# bitponics.net
KiCad netlist of a schematic drawn in EAGLE
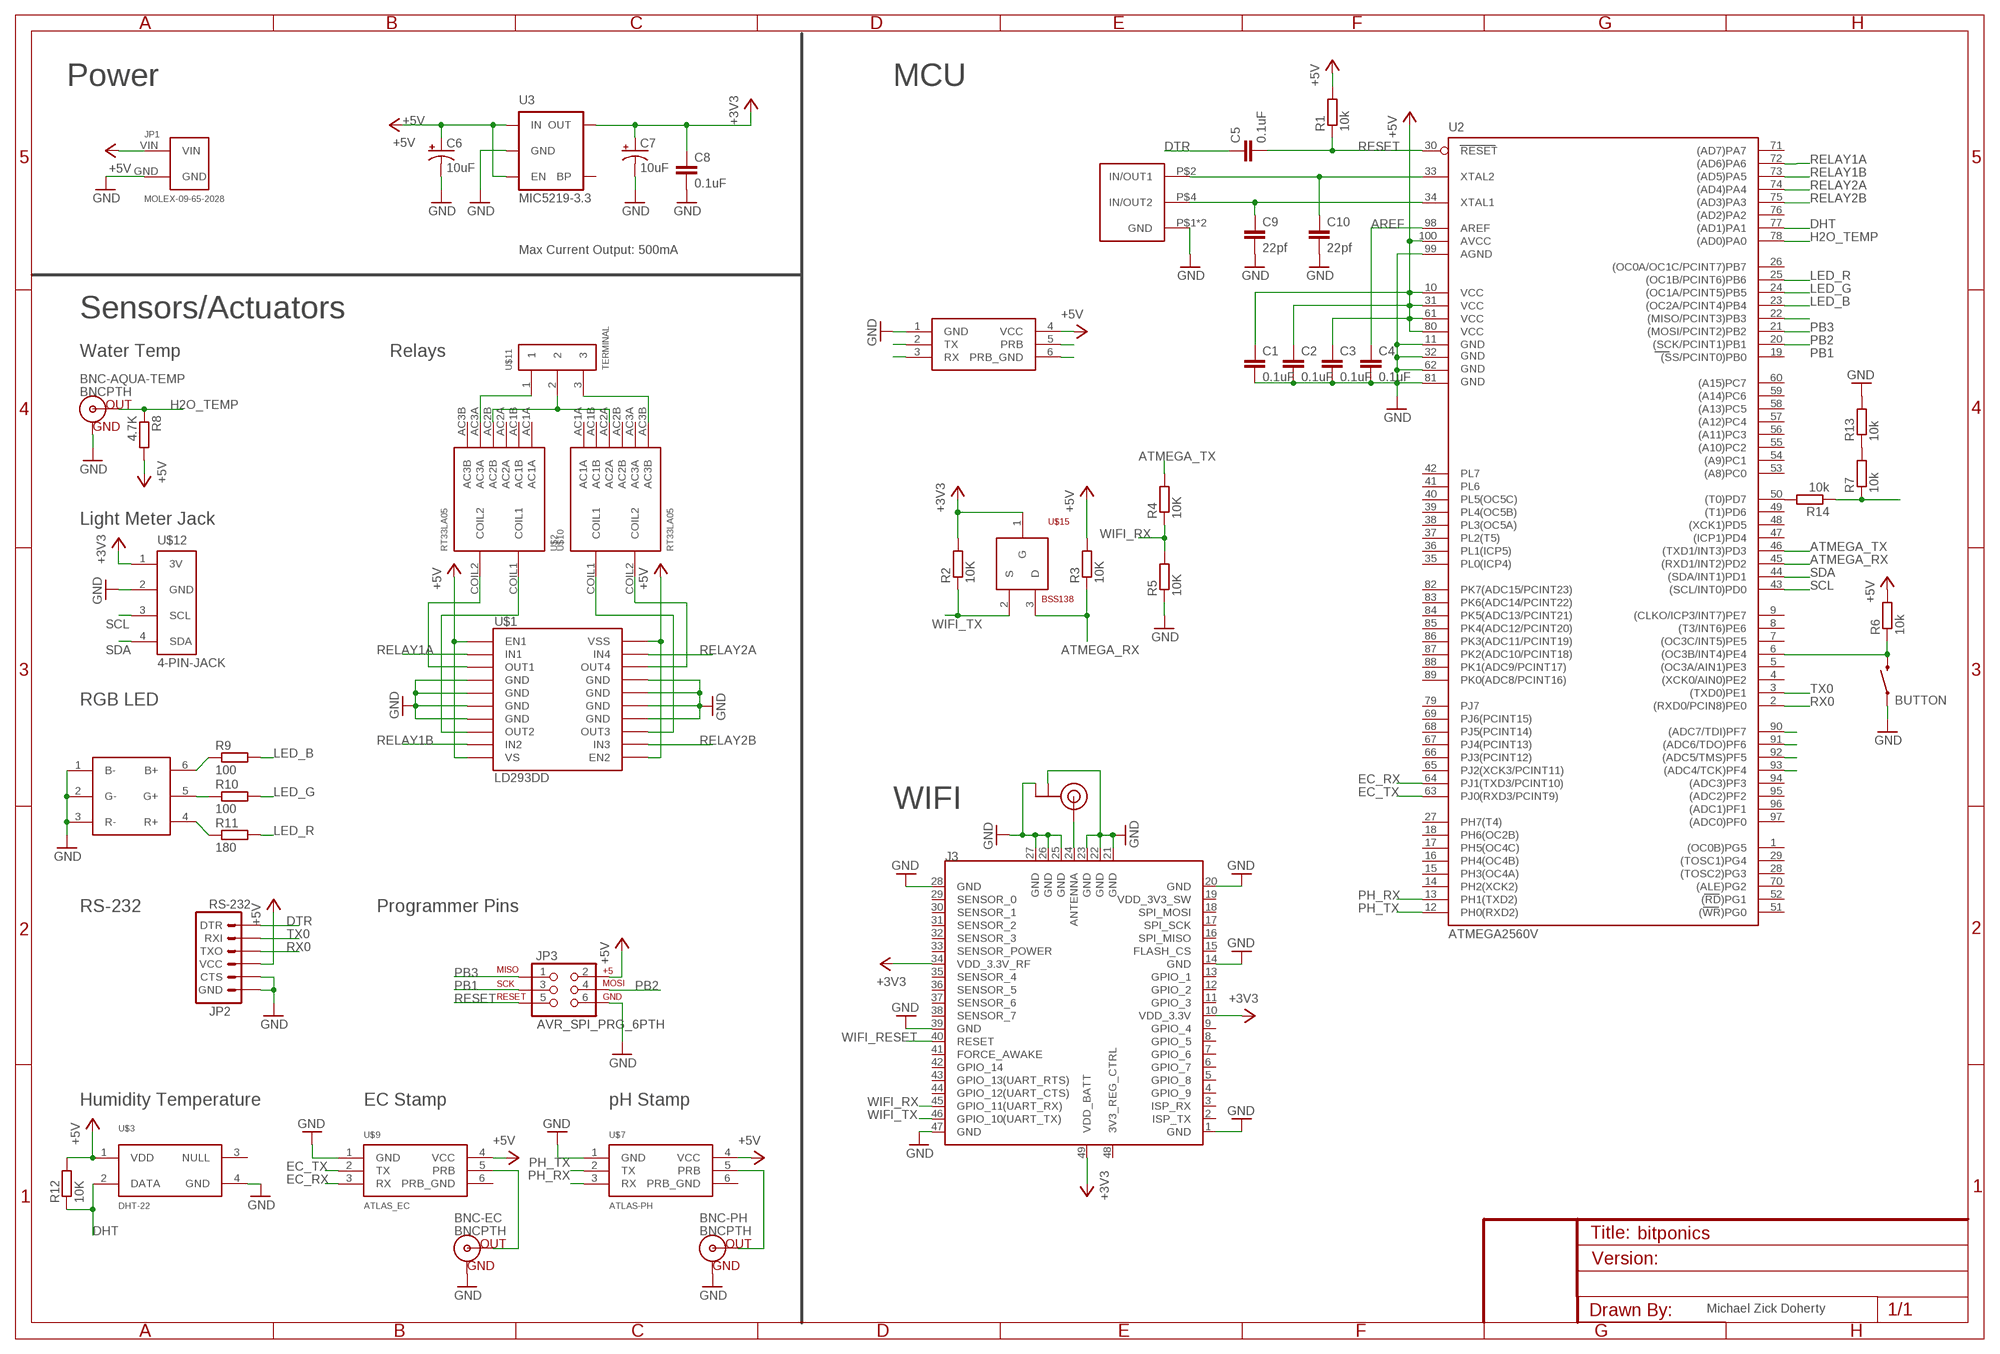
[diagram p0: schematic, sheet 1]

(export (version "E")
  (design (tool "Eeschema 10.0.6"))
  (components
    (comp (ref "BNC-AQUA-TEMP")
      (value "BNCPTH")
      (footprint "eagle-import:BNC")
      (libsource (lib "eagle-import") (part "BNCPTH"))
    )
    (comp (ref "BNC-EC")
      (value "BNCPTH")
      (footprint "eagle-import:BNC")
      (libsource (lib "eagle-import") (part "BNCPTH"))
    )
    (comp (ref "BNC-PH")
      (value "BNCPTH")
      (footprint "eagle-import:BNC")
      (libsource (lib "eagle-import") (part "BNCPTH"))
    )
    (comp (ref "BUTTON")
      (value "FSMRA2JH")
      (footprint "eagle-import:FSMRA2JH")
      (libsource (lib "eagle-import") (part "FSMRA2JH"))
    )
    (comp (ref "C1")
      (value "0.1uF")
      (footprint "eagle-import:C0603")
      (libsource (lib "eagle-import") (part "C-EUC0603"))
    )
    (comp (ref "C2")
      (value "0.1uF")
      (footprint "eagle-import:C0603")
      (libsource (lib "eagle-import") (part "C-EUC0603"))
    )
    (comp (ref "C3")
      (value "0.1uF")
      (footprint "eagle-import:C0603")
      (libsource (lib "eagle-import") (part "C-EUC0603"))
    )
    (comp (ref "C4")
      (value "0.1uF")
      (footprint "eagle-import:C0603")
      (libsource (lib "eagle-import") (part "C-EUC0603"))
    )
    (comp (ref "C5")
      (value "0.1uF")
      (footprint "eagle-import:C0603")
      (libsource (lib "eagle-import") (part "C-EUC0603"))
    )
    (comp (ref "C6")
      (value "10uF")
      (footprint "eagle-import:EIA3216")
      (libsource (lib "eagle-import") (part "CAP_POL1206"))
    )
    (comp (ref "C7")
      (value "10uF")
      (footprint "eagle-import:EIA3216")
      (libsource (lib "eagle-import") (part "CAP_POL1206"))
    )
    (comp (ref "C8")
      (value "0.1uF")
      (footprint "eagle-import:C0603")
      (libsource (lib "eagle-import") (part "C-EUC0603"))
    )
    (comp (ref "C9")
      (value "22pf")
      (footprint "eagle-import:C0603")
      (libsource (lib "eagle-import") (part "C-EUC0603"))
    )
    (comp (ref "C10")
      (value "22pf")
      (footprint "eagle-import:C0603")
      (libsource (lib "eagle-import") (part "C-EUC0603"))
    )
    (comp (ref "J3")
      (value "WIFI-RN-171")
      (footprint "eagle-import:49P-1.27-26.67X17.78")
      (libsource (lib "eagle-import") (part "WIFI-RN-171"))
    )
    (comp (ref "JP1")
      (value "MOLEX-09-65-2028")
      (footprint "eagle-import:09-65-2028")
      (libsource (lib "eagle-import") (part "MOLEX-09-65-2028"))
    )
    (comp (ref "JP2")
      (value "RS-232")
      (footprint "eagle-import:1X06_LOCK")
      (libsource (lib "eagle-import") (part "ARDUINO_SERIAL_PROGRAMLOCK"))
    )
    (comp (ref "JP3")
      (value "AVR_SPI_PRG_6PTH")
      (footprint "eagle-import:2X3")
      (libsource (lib "eagle-import") (part "AVR_SPI_PRG_6PTH"))
    )
    (comp (ref "R1")
      (value "10k")
      (footprint "eagle-import:R0603")
      (libsource (lib "eagle-import") (part "R-EU_R0603"))
    )
    (comp (ref "R2")
      (value "10K")
      (footprint "eagle-import:R0603")
      (libsource (lib "eagle-import") (part "R-EU_R0603"))
    )
    (comp (ref "R3")
      (value "10K")
      (footprint "eagle-import:R0603")
      (libsource (lib "eagle-import") (part "R-EU_R0603"))
    )
    (comp (ref "R4")
      (value "10K")
      (footprint "eagle-import:R0603")
      (libsource (lib "eagle-import") (part "R-EU_R0603"))
    )
    (comp (ref "R5")
      (value "10K")
      (footprint "eagle-import:R0603")
      (libsource (lib "eagle-import") (part "R-EU_R0603"))
    )
    (comp (ref "R6")
      (value "10k")
      (footprint "eagle-import:R0603")
      (libsource (lib "eagle-import") (part "R-EU_R0603"))
    )
    (comp (ref "R7")
      (value "10k")
      (footprint "eagle-import:R0603")
      (libsource (lib "eagle-import") (part "R-EU_R0603"))
    )
    (comp (ref "R8")
      (value "4.7K")
      (footprint "eagle-import:R0603")
      (libsource (lib "eagle-import") (part "R-EU_R0603"))
    )
    (comp (ref "R9")
      (value "100")
      (footprint "eagle-import:R0603")
      (libsource (lib "eagle-import") (part "R-EU_R0603"))
    )
    (comp (ref "R10")
      (value "100")
      (footprint "eagle-import:R0603")
      (libsource (lib "eagle-import") (part "R-EU_R0603"))
    )
    (comp (ref "R11")
      (value "180")
      (footprint "eagle-import:R0603")
      (libsource (lib "eagle-import") (part "R-EU_R0603"))
    )
    (comp (ref "R12")
      (value "10K")
      (footprint "eagle-import:R0603")
      (libsource (lib "eagle-import") (part "R-EU_R0603"))
    )
    (comp (ref "R13")
      (value "10k")
      (footprint "eagle-import:R0603")
      (libsource (lib "eagle-import") (part "R-EU_R0603"))
    )
    (comp (ref "R14")
      (value "10k")
      (footprint "eagle-import:R0603")
      (libsource (lib "eagle-import") (part "R-EU_R0603"))
    )
    (comp (ref "U$1")
      (value "LD293DD")
      (footprint "eagle-import:SO-20LD")
      (libsource (lib "eagle-import") (part "LD293DD"))
    )
    (comp (ref "U$2")
      (value "RT33LA05")
      (footprint "eagle-import:RT33LA05")
      (libsource (lib "eagle-import") (part "RT33LA05"))
    )
    (comp (ref "U$3")
      (value "DHT-22")
      (footprint "eagle-import:DHT22")
      (libsource (lib "eagle-import") (part "DHT-22"))
    )
    (comp (ref "U$4")
      (value "ATLAS-PH")
      (footprint "eagle-import:PH")
      (libsource (lib "eagle-import") (part "ATLAS-PH"))
    )
    (comp (ref "U$5")
      (value "U.FL")
      (footprint "eagle-import:U.FL")
      (libsource (lib "eagle-import") (part "U.FL"))
    )
    (comp (ref "U$6")
      (value "ECX-32")
      (footprint "eagle-import:ECX-32")
      (libsource (lib "eagle-import") (part "ECX-32"))
    )
    (comp (ref "U$7")
      (value "ATLAS-PH")
      (footprint "eagle-import:PH")
      (libsource (lib "eagle-import") (part "ATLAS-PH"))
    )
    (comp (ref "U$9")
      (value "ATLAS_EC")
      (footprint "eagle-import:EC")
      (libsource (lib "eagle-import") (part "ATLAS_EC"))
    )
    (comp (ref "U$10")
      (value "RT33LA05")
      (footprint "eagle-import:RT33LA05")
      (libsource (lib "eagle-import") (part "RT33LA05"))
    )
    (comp (ref "U$11")
      (value "TERMINAL")
      (footprint "eagle-import:TERMINAL")
      (libsource (lib "eagle-import") (part "TERMINAL"))
    )
    (comp (ref "U$12")
      (value "4-PIN-JACK")
      (footprint "eagle-import:4-PIN-JACK")
      (libsource (lib "eagle-import") (part "4-PIN-JACK"))
    )
    (comp (ref "U$15")
      (value "BSS138")
      (footprint "eagle-import:SOT23")
      (libsource (lib "eagle-import") (part "BSS138"))
    )
    (comp (ref "U2")
      (value "ATMEGA2560AU")
      (footprint "eagle-import:TQFP100")
      (libsource (lib "eagle-import") (part "ATMEGA2560AU"))
    )
    (comp (ref "U3")
      (value "V_REG_LDOSMD")
      (footprint "eagle-import:SOT23-5")
      (libsource (lib "eagle-import") (part "V_REG_LDOSMD"))
    )
    (comp (ref "U13")
      (value "RGB-LED")
      (footprint "eagle-import:RGB-LED")
      (libsource (lib "eagle-import") (part "RGB-LED"))
    )
  )
  (nets
    (net (code "1") (name "+3V3") (class "Default")
      (node (ref "C7") (pin "A") (pinfunction "+_A") (pintype "passive"))
      (node (ref "C8") (pin "1") (pinfunction "1_1") (pintype "passive"))
      (node (ref "J3") (pin "10") (pinfunction "VDD_3.3V_10") (pintype "power_in"))
      (node (ref "J3") (pin "34") (pinfunction "VDD_3.3V_RF_34") (pintype "power_in"))
      (node (ref "J3") (pin "49") (pinfunction "VDD_BATT_49") (pintype "bidirectional"))
      (node (ref "R2") (pin "2") (pinfunction "2_2") (pintype "passive"))
      (node (ref "U$12") (pin "1") (pinfunction "3V_1") (pintype "bidirectional"))
      (node (ref "U$15") (pin "1") (pinfunction "G_1") (pintype "bidirectional"))
      (node (ref "U3") (pin "5") (pinfunction "OUT_5") (pintype "passive"))
    )
    (net (code "2") (name "+5V") (class "Default")
      (node (ref "C1") (pin "1") (pinfunction "1_1") (pintype "passive"))
      (node (ref "C2") (pin "1") (pinfunction "1_1") (pintype "passive"))
      (node (ref "C3") (pin "1") (pinfunction "1_1") (pintype "passive"))
      (node (ref "C6") (pin "A") (pinfunction "+_A") (pintype "passive"))
      (node (ref "JP1") (pin "VIN") (pinfunction "VIN_VIN") (pintype "bidirectional"))
      (node (ref "JP2") (pin "4") (pinfunction "VCC_4") (pintype "passive"))
      (node (ref "JP3") (pin "2") (pinfunction "2_2") (pintype "passive"))
      (node (ref "R1") (pin "2") (pinfunction "2_2") (pintype "passive"))
      (node (ref "R12") (pin "2") (pinfunction "2_2") (pintype "passive"))
      (node (ref "R3") (pin "2") (pinfunction "2_2") (pintype "passive"))
      (node (ref "R6") (pin "2") (pinfunction "2_2") (pintype "passive"))
      (node (ref "R8") (pin "2") (pinfunction "2_2") (pintype "passive"))
      (node (ref "U$1") (pin "1") (pinfunction "EN1_1") (pintype "bidirectional"))
      (node (ref "U$1") (pin "10") (pinfunction "VS_10") (pintype "bidirectional"))
      (node (ref "U$1") (pin "11") (pinfunction "EN2_11") (pintype "bidirectional"))
      (node (ref "U$1") (pin "20") (pinfunction "VSS_20") (pintype "bidirectional"))
      (node (ref "U$3") (pin "1") (pinfunction "VDD_1") (pintype "bidirectional"))
      (node (ref "U$4") (pin "4") (pinfunction "VCC_4") (pintype "bidirectional"))
      (node (ref "U$7") (pin "4") (pinfunction "VCC_4") (pintype "bidirectional"))
      (node (ref "U$9") (pin "4") (pinfunction "VCC_4") (pintype "bidirectional"))
      (node (ref "U2") (pin "10") (pinfunction "VCC_10") (pintype "power_in"))
      (node (ref "U2") (pin "100") (pinfunction "AVCC_100") (pintype "power_in"))
      (node (ref "U2") (pin "31") (pinfunction "VCC1_31") (pintype "power_in"))
      (node (ref "U2") (pin "61") (pinfunction "VCC2_61") (pintype "power_in"))
      (node (ref "U2") (pin "80") (pinfunction "VCC3_80") (pintype "power_in"))
      (node (ref "U3") (pin "1") (pinfunction "IN_1") (pintype "input"))
      (node (ref "U3") (pin "3") (pinfunction "EN_3") (pintype "input"))
    )
    (net (code "3") (name "/A4") (class "Default")
      (node (ref "U$4") (pin "5") (pinfunction "PRB_5") (pintype "bidirectional"))
      (node (ref "U2") (pin "93") (pinfunction "(ADC4/TCK)PF4_93") (pintype "bidirectional"))
    )
    (net (code "4") (name "/A5") (class "Default")
      (node (ref "U$4") (pin "6") (pinfunction "PRB_GND_6") (pintype "bidirectional"))
      (node (ref "U2") (pin "92") (pinfunction "(ADC5/TMS)PF5_92") (pintype "bidirectional"))
    )
    (net (code "5") (name "/A6") (class "Default")
      (node (ref "U$4") (pin "3") (pinfunction "RX_3") (pintype "bidirectional"))
      (node (ref "U2") (pin "91") (pinfunction "(ADC6/TDO)PF6_91") (pintype "bidirectional"))
    )
    (net (code "6") (name "/A7") (class "Default")
      (node (ref "U$4") (pin "2") (pinfunction "TX_2") (pintype "bidirectional"))
      (node (ref "U2") (pin "90") (pinfunction "(ADC7/TDI)PF7_90") (pintype "bidirectional"))
    )
    (net (code "7") (name "/AREF") (class "Default")
      (node (ref "C4") (pin "1") (pinfunction "1_1") (pintype "passive"))
      (node (ref "U2") (pin "98") (pinfunction "AREF_98") (pintype "bidirectional"))
    )
    (net (code "8") (name "/ATMEGA_RX") (class "Default")
      (node (ref "R3") (pin "1") (pinfunction "1_1") (pintype "passive"))
      (node (ref "U$15") (pin "3") (pinfunction "D_3") (pintype "bidirectional"))
      (node (ref "U2") (pin "45") (pinfunction "(RXD1/INT2)PD2_45") (pintype "bidirectional"))
    )
    (net (code "9") (name "/ATMEGA_TX") (class "Default")
      (node (ref "R4") (pin "2") (pinfunction "2_2") (pintype "passive"))
      (node (ref "U2") (pin "46") (pinfunction "(TXD1/INT3)PD3_46") (pintype "bidirectional"))
    )
    (net (code "10") (name "/DHT") (class "Default")
      (node (ref "R12") (pin "1") (pinfunction "1_1") (pintype "passive"))
      (node (ref "U$3") (pin "2") (pinfunction "DATA_2") (pintype "bidirectional"))
      (node (ref "U2") (pin "77") (pinfunction "(AD1)PA1_77") (pintype "bidirectional"))
    )
    (net (code "11") (name "/DTR") (class "Default")
      (node (ref "C5") (pin "1") (pinfunction "1_1") (pintype "passive"))
      (node (ref "JP2") (pin "1") (pinfunction "DTR_1") (pintype "passive"))
    )
    (net (code "12") (name "/EC_RX") (class "Default")
      (node (ref "U$9") (pin "3") (pinfunction "RX_3") (pintype "bidirectional"))
      (node (ref "U2") (pin "64") (pinfunction "PJ1(TXD3/PCINT10)_64") (pintype "bidirectional"))
    )
    (net (code "13") (name "/EC_TX") (class "Default")
      (node (ref "U$9") (pin "2") (pinfunction "TX_2") (pintype "bidirectional"))
      (node (ref "U2") (pin "63") (pinfunction "PJ0(RXD3/PCINT9)_63") (pintype "bidirectional"))
    )
    (net (code "14") (name "/H2O_TEMP") (class "Default")
      (node (ref "BNC-AQUA-TEMP") (pin "S") (pinfunction "OUT_S") (pintype "bidirectional"))
      (node (ref "R8") (pin "1") (pinfunction "1_1") (pintype "passive"))
      (node (ref "U2") (pin "78") (pinfunction "(AD0)PA0_78") (pintype "bidirectional"))
    )
    (net (code "15") (name "/LED_B") (class "Default")
      (node (ref "R9") (pin "2") (pinfunction "2_2") (pintype "passive"))
      (node (ref "U2") (pin "23") (pinfunction "(OC2A/PCINT4)PB4_23") (pintype "bidirectional"))
    )
    (net (code "16") (name "/LED_G") (class "Default")
      (node (ref "R10") (pin "2") (pinfunction "2_2") (pintype "passive"))
      (node (ref "U2") (pin "24") (pinfunction "(OC1A/PCINT5)PB5_24") (pintype "bidirectional"))
    )
    (net (code "17") (name "/LED_R") (class "Default")
      (node (ref "R11") (pin "2") (pinfunction "2_2") (pintype "passive"))
      (node (ref "U2") (pin "25") (pinfunction "(OC1B/PCINT6)PB6_25") (pintype "bidirectional"))
    )
    (net (code "18") (name "/PB1") (class "Default")
      (node (ref "JP3") (pin "3") (pinfunction "3_3") (pintype "passive"))
      (node (ref "U2") (pin "20") (pinfunction "(SCK/PCINT1)PB1_20") (pintype "bidirectional"))
    )
    (net (code "19") (name "/PB2") (class "Default")
      (node (ref "JP3") (pin "4") (pinfunction "4_4") (pintype "passive"))
      (node (ref "U2") (pin "21") (pinfunction "(MOSI/PCINT2)PB2_21") (pintype "bidirectional"))
    )
    (net (code "20") (name "/PB3") (class "Default")
      (node (ref "JP3") (pin "1") (pinfunction "1_1") (pintype "passive"))
      (node (ref "U2") (pin "22") (pinfunction "(MISO/PCINT3)PB3_22") (pintype "bidirectional"))
    )
    (net (code "21") (name "/PH_RX") (class "Default")
      (node (ref "U$7") (pin "3") (pinfunction "RX_3") (pintype "bidirectional"))
      (node (ref "U2") (pin "13") (pinfunction "PH1(TXD2)_13") (pintype "bidirectional"))
    )
    (net (code "22") (name "/PH_TX") (class "Default")
      (node (ref "U$7") (pin "2") (pinfunction "TX_2") (pintype "bidirectional"))
      (node (ref "U2") (pin "12") (pinfunction "PH0(RXD2)_12") (pintype "bidirectional"))
    )
    (net (code "23") (name "/RELAY1A") (class "Default")
      (node (ref "U$1") (pin "2") (pinfunction "IN1_2") (pintype "bidirectional"))
      (node (ref "U2") (pin "72") (pinfunction "(AD6)PA6_72") (pintype "bidirectional"))
    )
    (net (code "24") (name "/RELAY1B") (class "Default")
      (node (ref "U$1") (pin "9") (pinfunction "IN2_9") (pintype "bidirectional"))
      (node (ref "U2") (pin "73") (pinfunction "(AD5)PA5_73") (pintype "bidirectional"))
    )
    (net (code "25") (name "/RELAY2A") (class "Default")
      (node (ref "U$1") (pin "19") (pinfunction "IN4_19") (pintype "bidirectional"))
      (node (ref "U2") (pin "74") (pinfunction "(AD4)PA4_74") (pintype "bidirectional"))
    )
    (net (code "26") (name "/RELAY2B") (class "Default")
      (node (ref "U$1") (pin "12") (pinfunction "IN3_12") (pintype "bidirectional"))
      (node (ref "U2") (pin "75") (pinfunction "(AD3)PA3_75") (pintype "bidirectional"))
    )
    (net (code "27") (name "/RESET") (class "Default")
      (node (ref "C5") (pin "2") (pinfunction "2_2") (pintype "passive"))
      (node (ref "JP3") (pin "5") (pinfunction "5_5") (pintype "passive"))
      (node (ref "R1") (pin "1") (pinfunction "1_1") (pintype "passive"))
      (node (ref "U2") (pin "30") (pinfunction "RESET_30") (pintype "input"))
    )
    (net (code "28") (name "/RX0") (class "Default")
      (node (ref "JP2") (pin "3") (pinfunction "TXO_3") (pintype "passive"))
      (node (ref "U2") (pin "2") (pinfunction "(RXD0/PCIN8)PE0_2") (pintype "bidirectional"))
    )
    (net (code "29") (name "/SCL") (class "Default")
      (node (ref "U$12") (pin "3") (pinfunction "SCL_3") (pintype "bidirectional"))
      (node (ref "U2") (pin "43") (pinfunction "(SCL/INT0)PD0_43") (pintype "bidirectional"))
    )
    (net (code "30") (name "/SDA") (class "Default")
      (node (ref "U$12") (pin "4") (pinfunction "SDA_4") (pintype "bidirectional"))
      (node (ref "U2") (pin "44") (pinfunction "(SDA/INT1)PD1_44") (pintype "bidirectional"))
    )
    (net (code "31") (name "/TX0") (class "Default")
      (node (ref "JP2") (pin "2") (pinfunction "RXI_2") (pintype "passive"))
      (node (ref "U2") (pin "3") (pinfunction "(TXD0)PE1_3") (pintype "bidirectional"))
    )
    (net (code "32") (name "/WIFI_RESET") (class "Default")
      (node (ref "J3") (pin "40") (pinfunction "RESET_40") (pintype "input"))
      (node (ref "R14") (pin "1") (pinfunction "1_1") (pintype "passive"))
      (node (ref "R7") (pin "1") (pinfunction "1_1") (pintype "passive"))
    )
    (net (code "33") (name "/WIFI_RX") (class "Default")
      (node (ref "J3") (pin "45") (pinfunction "GPIO_11(UART_RX)_45") (pintype "bidirectional"))
      (node (ref "R4") (pin "1") (pinfunction "1_1") (pintype "passive"))
      (node (ref "R5") (pin "2") (pinfunction "2_2") (pintype "passive"))
    )
    (net (code "34") (name "/WIFI_TX") (class "Default")
      (node (ref "J3") (pin "46") (pinfunction "GPIO_10(UART_TX)_46") (pintype "bidirectional"))
      (node (ref "R2") (pin "1") (pinfunction "1_1") (pintype "passive"))
      (node (ref "U$15") (pin "2") (pinfunction "S_2") (pintype "bidirectional"))
    )
    (net (code "35") (name "GND") (class "Default")
      (node (ref "BNC-AQUA-TEMP") (pin "GND") (pinfunction "GND_GND") (pintype "bidirectional"))
      (node (ref "BNC-EC") (pin "GND") (pinfunction "GND_GND") (pintype "bidirectional"))
      (node (ref "BNC-PH") (pin "GND") (pinfunction "GND_GND") (pintype "bidirectional"))
      (node (ref "BUTTON") (pin "2A") (pinfunction "1_2A") (pintype "passive"))
      (node (ref "C1") (pin "2") (pinfunction "2_2") (pintype "passive"))
      (node (ref "C10") (pin "2") (pinfunction "2_2") (pintype "passive"))
      (node (ref "C2") (pin "2") (pinfunction "2_2") (pintype "passive"))
      (node (ref "C3") (pin "2") (pinfunction "2_2") (pintype "passive"))
      (node (ref "C4") (pin "2") (pinfunction "2_2") (pintype "passive"))
      (node (ref "C6") (pin "C") (pinfunction "-_C") (pintype "passive"))
      (node (ref "C7") (pin "C") (pinfunction "-_C") (pintype "passive"))
      (node (ref "C8") (pin "2") (pinfunction "2_2") (pintype "passive"))
      (node (ref "C9") (pin "2") (pinfunction "2_2") (pintype "passive"))
      (node (ref "J3") (pin "1") (pinfunction "GND_1") (pintype "power_in"))
      (node (ref "J3") (pin "14") (pinfunction "GND_14") (pintype "power_in"))
      (node (ref "J3") (pin "20") (pinfunction "GND_20") (pintype "power_in"))
      (node (ref "J3") (pin "21") (pinfunction "GND_21") (pintype "power_in"))
      (node (ref "J3") (pin "22") (pinfunction "GND_22") (pintype "power_in"))
      (node (ref "J3") (pin "23") (pinfunction "GND_23") (pintype "power_in"))
      (node (ref "J3") (pin "25") (pinfunction "GND_25") (pintype "power_in"))
      (node (ref "J3") (pin "26") (pinfunction "GND_26") (pintype "power_in"))
      (node (ref "J3") (pin "27") (pinfunction "GND_27") (pintype "power_in"))
      (node (ref "J3") (pin "28") (pinfunction "GND_28") (pintype "power_in"))
      (node (ref "J3") (pin "39") (pinfunction "GND_39") (pintype "power_in"))
      (node (ref "J3") (pin "47") (pinfunction "GND_47") (pintype "power_in"))
      (node (ref "JP1") (pin "GND") (pinfunction "GND_GND") (pintype "bidirectional"))
      (node (ref "JP2") (pin "5") (pinfunction "CTS_5") (pintype "passive"))
      (node (ref "JP2") (pin "6") (pinfunction "GND_6") (pintype "passive"))
      (node (ref "JP3") (pin "6") (pinfunction "6_6") (pintype "passive"))
      (node (ref "R13") (pin "2") (pinfunction "2_2") (pintype "passive"))
      (node (ref "R5") (pin "1") (pinfunction "1_1") (pintype "passive"))
      (node (ref "U$1") (pin "14") (pinfunction "GND_14") (pintype "bidirectional"))
      (node (ref "U$1") (pin "15") (pinfunction "GND_15") (pintype "bidirectional"))
      (node (ref "U$1") (pin "16") (pinfunction "GND_16") (pintype "bidirectional"))
      (node (ref "U$1") (pin "17") (pinfunction "GND_17") (pintype "bidirectional"))
      (node (ref "U$1") (pin "4") (pinfunction "GND_4") (pintype "bidirectional"))
      (node (ref "U$1") (pin "5") (pinfunction "GND_5") (pintype "bidirectional"))
      (node (ref "U$1") (pin "6") (pinfunction "GND_6") (pintype "bidirectional"))
      (node (ref "U$1") (pin "7") (pinfunction "GND_7") (pintype "bidirectional"))
      (node (ref "U$12") (pin "2") (pinfunction "GND_2") (pintype "bidirectional"))
      (node (ref "U$3") (pin "4") (pinfunction "GND_4") (pintype "bidirectional"))
      (node (ref "U$4") (pin "1") (pinfunction "GND_1") (pintype "bidirectional"))
      (node (ref "U$5") (pin "P$1") (pinfunction "GND_P$1") (pintype "bidirectional"))
      (node (ref "U$5") (pin "P$2") (pinfunction "GND_P$2") (pintype "bidirectional"))
      (node (ref "U$6") (pin "P$1") (pinfunction "GND_P$1") (pintype "bidirectional"))
      (node (ref "U$6") (pin "P$3") (pinfunction "GND_P$3") (pintype "bidirectional"))
      (node (ref "U$7") (pin "1") (pinfunction "GND_1") (pintype "bidirectional"))
      (node (ref "U$9") (pin "1") (pinfunction "GND_1") (pintype "bidirectional"))
      (node (ref "U13") (pin "1") (pinfunction "B-_1") (pintype "bidirectional"))
      (node (ref "U13") (pin "2") (pinfunction "G-_2") (pintype "bidirectional"))
      (node (ref "U13") (pin "3") (pinfunction "R-_3") (pintype "bidirectional"))
      (node (ref "U2") (pin "11") (pinfunction "GND_11") (pintype "power_in"))
      (node (ref "U2") (pin "32") (pinfunction "GND1_32") (pintype "power_in"))
      (node (ref "U2") (pin "62") (pinfunction "GND2_62") (pintype "power_in"))
      (node (ref "U2") (pin "81") (pinfunction "GND3_81") (pintype "power_in"))
      (node (ref "U2") (pin "99") (pinfunction "AGND_99") (pintype "power_in"))
      (node (ref "U3") (pin "2") (pinfunction "GND_2") (pintype "input"))
    )
    (net (code "36") (name "Net-(BNC-EC-OUT)") (class "Default")
      (node (ref "BNC-EC") (pin "S") (pinfunction "OUT_S") (pintype "bidirectional"))
      (node (ref "U$9") (pin "5") (pinfunction "PRB_5") (pintype "bidirectional"))
    )
    (net (code "37") (name "Net-(BNC-PH-OUT)") (class "Default")
      (node (ref "BNC-PH") (pin "S") (pinfunction "OUT_S") (pintype "bidirectional"))
      (node (ref "U$7") (pin "5") (pinfunction "PRB_5") (pintype "bidirectional"))
    )
    (net (code "38") (name "Net-(BUTTON-2)") (class "Default")
      (node (ref "BUTTON") (pin "2B") (pinfunction "2_2B") (pintype "passive"))
      (node (ref "R6") (pin "1") (pinfunction "1_1") (pintype "passive"))
      (node (ref "U2") (pin "6") (pinfunction "(OC3B/INT4)PE4_6") (pintype "bidirectional"))
    )
    (net (code "39") (name "Net-(J3-ANTENNA)") (class "Default")
      (node (ref "J3") (pin "24") (pinfunction "ANTENNA_24") (pintype "bidirectional"))
      (node (ref "U$5") (pin "P$3") (pinfunction "SIGNAL_P$3") (pintype "bidirectional"))
    )
    (net (code "40") (name "Net-(R13-Pad1)") (class "Default")
      (node (ref "R13") (pin "1") (pinfunction "1_1") (pintype "passive"))
      (node (ref "R7") (pin "2") (pinfunction "2_2") (pintype "passive"))
    )
    (net (code "41") (name "Net-(U$1-OUT1)") (class "Default")
      (node (ref "U$1") (pin "3") (pinfunction "OUT1_3") (pintype "bidirectional"))
      (node (ref "U$2") (pin "COIL2") (pinfunction "COIL2_COIL2") (pintype "bidirectional"))
    )
    (net (code "42") (name "Net-(U$1-OUT2)") (class "Default")
      (node (ref "U$1") (pin "8") (pinfunction "OUT2_8") (pintype "bidirectional"))
      (node (ref "U$2") (pin "COIL1") (pinfunction "COIL1_COIL1") (pintype "bidirectional"))
    )
    (net (code "43") (name "Net-(U$1-OUT3)") (class "Default")
      (node (ref "U$1") (pin "13") (pinfunction "OUT3_13") (pintype "bidirectional"))
      (node (ref "U$10") (pin "COIL1") (pinfunction "COIL1_COIL1") (pintype "bidirectional"))
    )
    (net (code "44") (name "Net-(U$1-OUT4)") (class "Default")
      (node (ref "U$1") (pin "18") (pinfunction "OUT4_18") (pintype "bidirectional"))
      (node (ref "U$10") (pin "COIL2") (pinfunction "COIL2_COIL2") (pintype "bidirectional"))
    )
    (net (code "45") (name "Net-(U$6-IN{slash}OUT1)") (class "Default")
      (node (ref "C10") (pin "1") (pinfunction "1_1") (pintype "passive"))
      (node (ref "U$6") (pin "P$2") (pinfunction "IN/OUT1_P$2") (pintype "bidirectional"))
      (node (ref "U2") (pin "33") (pinfunction "XTAL2_33") (pintype "output"))
    )
    (net (code "46") (name "Net-(U$6-IN{slash}OUT2)") (class "Default")
      (node (ref "C9") (pin "1") (pinfunction "1_1") (pintype "passive"))
      (node (ref "U$6") (pin "P$4") (pinfunction "IN/OUT2_P$4") (pintype "bidirectional"))
      (node (ref "U2") (pin "34") (pinfunction "XTAL1_34") (pintype "input"))
    )
    (net (code "47") (name "Net-(U$10-PadAC2A)") (class "Default")
      (node (ref "U$10") (pin "AC2A") (pinfunction "AC2A_AC2A") (pintype "bidirectional"))
      (node (ref "U$11") (pin "2") (pinfunction "2_2") (pintype "bidirectional"))
      (node (ref "U$2") (pin "AC2B") (pinfunction "AC2B_AC2B") (pintype "bidirectional"))
    )
    (net (code "48") (name "Net-(U$10-PadAC3B)") (class "Default")
      (node (ref "U$10") (pin "AC3B") (pinfunction "AC3B_AC3B") (pintype "bidirectional"))
      (node (ref "U$11") (pin "3") (pinfunction "3_3") (pintype "bidirectional"))
    )
    (net (code "49") (name "Net-(U$11-Pad1)") (class "Default")
      (node (ref "U$11") (pin "1") (pinfunction "1_1") (pintype "bidirectional"))
      (node (ref "U$2") (pin "AC3A") (pinfunction "AC3A_AC3A") (pintype "bidirectional"))
    )
    (net (code "50") (name "Net-(U2-(T0)PD7)") (class "Default")
      (node (ref "R14") (pin "2") (pinfunction "2_2") (pintype "passive"))
      (node (ref "U2") (pin "50") (pinfunction "(T0)PD7_50") (pintype "bidirectional"))
    )
    (net (code "51") (name "Net-(U13-B+)") (class "Default")
      (node (ref "R9") (pin "1") (pinfunction "1_1") (pintype "passive"))
      (node (ref "U13") (pin "6") (pinfunction "B+_6") (pintype "bidirectional"))
    )
    (net (code "52") (name "Net-(U13-G+)") (class "Default")
      (node (ref "R10") (pin "1") (pinfunction "1_1") (pintype "passive"))
      (node (ref "U13") (pin "5") (pinfunction "G+_5") (pintype "bidirectional"))
    )
    (net (code "53") (name "Net-(U13-R+)") (class "Default")
      (node (ref "R11") (pin "1") (pinfunction "1_1") (pintype "passive"))
      (node (ref "U13") (pin "4") (pinfunction "R+_4") (pintype "bidirectional"))
    )
    (net (code "54") (name "unconnected-(J3-3V3_REG_CTRL-Pad48)") (class "Default")
      (node (ref "J3") (pin "48") (pinfunction "3V3_REG_CTRL_48") (pintype "input"))
    )
    (net (code "55") (name "unconnected-(J3-FLASH_CS-Pad15)") (class "Default")
      (node (ref "J3") (pin "15") (pinfunction "FLASH_CS_15") (pintype "bidirectional"))
    )
    (net (code "56") (name "unconnected-(J3-FORCE_AWAKE-Pad41)") (class "Default")
      (node (ref "J3") (pin "41") (pinfunction "FORCE_AWAKE_41") (pintype "bidirectional"))
    )
    (net (code "57") (name "unconnected-(J3-GPIO_1-Pad13)") (class "Default")
      (node (ref "J3") (pin "13") (pinfunction "GPIO_1_13") (pintype "bidirectional"))
    )
    (net (code "58") (name "unconnected-(J3-GPIO_2-Pad12)") (class "Default")
      (node (ref "J3") (pin "12") (pinfunction "GPIO_2_12") (pintype "bidirectional"))
    )
    (net (code "59") (name "unconnected-(J3-GPIO_3-Pad11)") (class "Default")
      (node (ref "J3") (pin "11") (pinfunction "GPIO_3_11") (pintype "bidirectional"))
    )
    (net (code "60") (name "unconnected-(J3-GPIO_4-Pad9)") (class "Default")
      (node (ref "J3") (pin "9") (pinfunction "GPIO_4_9") (pintype "bidirectional"))
    )
    (net (code "61") (name "unconnected-(J3-GPIO_5-Pad8)") (class "Default")
      (node (ref "J3") (pin "8") (pinfunction "GPIO_5_8") (pintype "bidirectional"))
    )
    (net (code "62") (name "unconnected-(J3-GPIO_6-Pad7)") (class "Default")
      (node (ref "J3") (pin "7") (pinfunction "GPIO_6_7") (pintype "bidirectional"))
    )
    (net (code "63") (name "unconnected-(J3-GPIO_7-Pad6)") (class "Default")
      (node (ref "J3") (pin "6") (pinfunction "GPIO_7_6") (pintype "bidirectional"))
    )
    (net (code "64") (name "unconnected-(J3-GPIO_8-Pad5)") (class "Default")
      (node (ref "J3") (pin "5") (pinfunction "GPIO_8_5") (pintype "bidirectional"))
    )
    (net (code "65") (name "unconnected-(J3-GPIO_9-Pad4)") (class "Default")
      (node (ref "J3") (pin "4") (pinfunction "GPIO_9_4") (pintype "bidirectional"))
    )
    (net (code "66") (name "unconnected-(J3-GPIO_12(UART_CTS)-Pad44)") (class "Default")
      (node (ref "J3") (pin "44") (pinfunction "GPIO_12(UART_CTS)_44") (pintype "bidirectional"))
    )
    (net (code "67") (name "unconnected-(J3-GPIO_13(UART_RTS)-Pad43)") (class "Default")
      (node (ref "J3") (pin "43") (pinfunction "GPIO_13(UART_RTS)_43") (pintype "bidirectional"))
    )
    (net (code "68") (name "unconnected-(J3-GPIO_14-Pad42)") (class "Default")
      (node (ref "J3") (pin "42") (pinfunction "GPIO_14_42") (pintype "bidirectional"))
    )
    (net (code "69") (name "unconnected-(J3-ISP_RX-Pad3)") (class "Default")
      (node (ref "J3") (pin "3") (pinfunction "ISP_RX_3") (pintype "bidirectional"))
    )
    (net (code "70") (name "unconnected-(J3-ISP_TX-Pad2)") (class "Default")
      (node (ref "J3") (pin "2") (pinfunction "ISP_TX_2") (pintype "bidirectional"))
    )
    (net (code "71") (name "unconnected-(J3-SENSOR_0-Pad29)") (class "Default")
      (node (ref "J3") (pin "29") (pinfunction "SENSOR_0_29") (pintype "input"))
    )
    (net (code "72") (name "unconnected-(J3-SENSOR_1-Pad30)") (class "Default")
      (node (ref "J3") (pin "30") (pinfunction "SENSOR_1_30") (pintype "input"))
    )
    (net (code "73") (name "unconnected-(J3-SENSOR_2-Pad31)") (class "Default")
      (node (ref "J3") (pin "31") (pinfunction "SENSOR_2_31") (pintype "input"))
    )
    (net (code "74") (name "unconnected-(J3-SENSOR_3-Pad32)") (class "Default")
      (node (ref "J3") (pin "32") (pinfunction "SENSOR_3_32") (pintype "input"))
    )
    (net (code "75") (name "unconnected-(J3-SENSOR_4-Pad35)") (class "Default")
      (node (ref "J3") (pin "35") (pinfunction "SENSOR_4_35") (pintype "input"))
    )
    (net (code "76") (name "unconnected-(J3-SENSOR_5-Pad36)") (class "Default")
      (node (ref "J3") (pin "36") (pinfunction "SENSOR_5_36") (pintype "input"))
    )
    (net (code "77") (name "unconnected-(J3-SENSOR_6-Pad37)") (class "Default")
      (node (ref "J3") (pin "37") (pinfunction "SENSOR_6_37") (pintype "input"))
    )
    (net (code "78") (name "unconnected-(J3-SENSOR_7-Pad38)") (class "Default")
      (node (ref "J3") (pin "38") (pinfunction "SENSOR_7_38") (pintype "input"))
    )
    (net (code "79") (name "unconnected-(J3-SENSOR_POWER-Pad33)") (class "Default")
      (node (ref "J3") (pin "33") (pinfunction "SENSOR_POWER_33") (pintype "output"))
    )
    (net (code "80") (name "unconnected-(J3-SPI_MISO-Pad16)") (class "Default")
      (node (ref "J3") (pin "16") (pinfunction "SPI_MISO_16") (pintype "bidirectional"))
    )
    (net (code "81") (name "unconnected-(J3-SPI_MOSI-Pad18)") (class "Default")
      (node (ref "J3") (pin "18") (pinfunction "SPI_MOSI_18") (pintype "bidirectional"))
    )
    (net (code "82") (name "unconnected-(J3-SPI_SCK-Pad17)") (class "Default")
      (node (ref "J3") (pin "17") (pinfunction "SPI_SCK_17") (pintype "bidirectional"))
    )
    (net (code "83") (name "unconnected-(J3-VDD_3V3_SW-Pad19)") (class "Default")
      (node (ref "J3") (pin "19") (pinfunction "VDD_3V3_SW_19") (pintype "bidirectional"))
    )
    (net (code "84") (name "unconnected-(U$2-PadAC1A)") (class "Default")
      (node (ref "U$2") (pin "AC1A") (pinfunction "AC1A_AC1A") (pintype "bidirectional"))
    )
    (net (code "85") (name "unconnected-(U$2-PadAC1B)") (class "Default")
      (node (ref "U$2") (pin "AC1B") (pinfunction "AC1B_AC1B") (pintype "bidirectional"))
    )
    (net (code "86") (name "unconnected-(U$2-PadAC2A)") (class "Default")
      (node (ref "U$2") (pin "AC2A") (pinfunction "AC2A_AC2A") (pintype "bidirectional"))
    )
    (net (code "87") (name "unconnected-(U$2-PadAC3B)") (class "Default")
      (node (ref "U$2") (pin "AC3B") (pinfunction "AC3B_AC3B") (pintype "bidirectional"))
    )
    (net (code "88") (name "unconnected-(U$3-NULL-Pad3)") (class "Default")
      (node (ref "U$3") (pin "3") (pinfunction "NULL_3") (pintype "bidirectional"))
    )
    (net (code "89") (name "unconnected-(U$7-PRB_GND-Pad6)") (class "Default")
      (node (ref "U$7") (pin "6") (pinfunction "PRB_GND_6") (pintype "bidirectional"))
    )
    (net (code "90") (name "unconnected-(U$9-PRB_GND-Pad6)") (class "Default")
      (node (ref "U$9") (pin "6") (pinfunction "PRB_GND_6") (pintype "bidirectional"))
    )
    (net (code "91") (name "unconnected-(U$10-PadAC1A)") (class "Default")
      (node (ref "U$10") (pin "AC1A") (pinfunction "AC1A_AC1A") (pintype "bidirectional"))
    )
    (net (code "92") (name "unconnected-(U$10-PadAC1B)") (class "Default")
      (node (ref "U$10") (pin "AC1B") (pinfunction "AC1B_AC1B") (pintype "bidirectional"))
    )
    (net (code "93") (name "unconnected-(U$10-PadAC2B)") (class "Default")
      (node (ref "U$10") (pin "AC2B") (pinfunction "AC2B_AC2B") (pintype "bidirectional"))
    )
    (net (code "94") (name "unconnected-(U$10-PadAC3A)") (class "Default")
      (node (ref "U$10") (pin "AC3A") (pinfunction "AC3A_AC3A") (pintype "bidirectional"))
    )
    (net (code "95") (name "unconnected-(U2-(A8)PC0-Pad53)") (class "Default")
      (node (ref "U2") (pin "53") (pinfunction "(A8)PC0_53") (pintype "bidirectional"))
    )
    (net (code "96") (name "unconnected-(U2-(A9)PC1-Pad54)") (class "Default")
      (node (ref "U2") (pin "54") (pinfunction "(A9)PC1_54") (pintype "bidirectional"))
    )
    (net (code "97") (name "unconnected-(U2-(A10)PC2-Pad55)") (class "Default")
      (node (ref "U2") (pin "55") (pinfunction "(A10)PC2_55") (pintype "bidirectional"))
    )
    (net (code "98") (name "unconnected-(U2-(A11)PC3-Pad56)") (class "Default")
      (node (ref "U2") (pin "56") (pinfunction "(A11)PC3_56") (pintype "bidirectional"))
    )
    (net (code "99") (name "unconnected-(U2-(A12)PC4-Pad57)") (class "Default")
      (node (ref "U2") (pin "57") (pinfunction "(A12)PC4_57") (pintype "bidirectional"))
    )
    (net (code "100") (name "unconnected-(U2-(A13)PC5-Pad58)") (class "Default")
      (node (ref "U2") (pin "58") (pinfunction "(A13)PC5_58") (pintype "bidirectional"))
    )
    (net (code "101") (name "unconnected-(U2-(A14)PC6-Pad59)") (class "Default")
      (node (ref "U2") (pin "59") (pinfunction "(A14)PC6_59") (pintype "bidirectional"))
    )
    (net (code "102") (name "unconnected-(U2-(A15)PC7-Pad60)") (class "Default")
      (node (ref "U2") (pin "60") (pinfunction "(A15)PC7_60") (pintype "bidirectional"))
    )
    (net (code "103") (name "unconnected-(U2-(AD2)PA2-Pad76)") (class "Default")
      (node (ref "U2") (pin "76") (pinfunction "(AD2)PA2_76") (pintype "bidirectional"))
    )
    (net (code "104") (name "unconnected-(U2-(AD7)PA7-Pad71)") (class "Default")
      (node (ref "U2") (pin "71") (pinfunction "(AD7)PA7_71") (pintype "bidirectional"))
    )
    (net (code "105") (name "unconnected-(U2-(ADC0)PF0-Pad97)") (class "Default")
      (node (ref "U2") (pin "97") (pinfunction "(ADC0)PF0_97") (pintype "bidirectional"))
    )
    (net (code "106") (name "unconnected-(U2-(ADC1)PF1-Pad96)") (class "Default")
      (node (ref "U2") (pin "96") (pinfunction "(ADC1)PF1_96") (pintype "bidirectional"))
    )
    (net (code "107") (name "unconnected-(U2-(ADC2)PF2-Pad95)") (class "Default")
      (node (ref "U2") (pin "95") (pinfunction "(ADC2)PF2_95") (pintype "bidirectional"))
    )
    (net (code "108") (name "unconnected-(U2-(ADC3)PF3-Pad94)") (class "Default")
      (node (ref "U2") (pin "94") (pinfunction "(ADC3)PF3_94") (pintype "bidirectional"))
    )
    (net (code "109") (name "unconnected-(U2-(ALE)PG2-Pad70)") (class "Default")
      (node (ref "U2") (pin "70") (pinfunction "(ALE)PG2_70") (pintype "bidirectional"))
    )
    (net (code "110") (name "unconnected-(U2-(CLKO{slash}ICP3{slash}INT7)PE7-Pad9)") (class "Default")
      (node (ref "U2") (pin "9") (pinfunction "(CLKO/ICP3/INT7)PE7_9") (pintype "bidirectional"))
    )
    (net (code "111") (name "unconnected-(U2-(ICP1)PD4-Pad47)") (class "Default")
      (node (ref "U2") (pin "47") (pinfunction "(ICP1)PD4_47") (pintype "bidirectional"))
    )
    (net (code "112") (name "unconnected-(U2-(OC0A{slash}OC1C{slash}PCINT7)PB7-Pad26)") (class "Default")
      (node (ref "U2") (pin "26") (pinfunction "(OC0A/OC1C/PCINT7)PB7_26") (pintype "bidirectional"))
    )
    (net (code "113") (name "unconnected-(U2-(OC0B)PG5-Pad1)") (class "Default")
      (node (ref "U2") (pin "1") (pinfunction "(OC0B)PG5_1") (pintype "bidirectional"))
    )
    (net (code "114") (name "unconnected-(U2-(OC3A{slash}AIN1)PE3-Pad5)") (class "Default")
      (node (ref "U2") (pin "5") (pinfunction "(OC3A/AIN1)PE3_5") (pintype "bidirectional"))
    )
    (net (code "115") (name "unconnected-(U2-(OC3C{slash}INT5)PE5-Pad7)") (class "Default")
      (node (ref "U2") (pin "7") (pinfunction "(OC3C/INT5)PE5_7") (pintype "bidirectional"))
    )
    (net (code "116") (name "unconnected-(U2-(RD)PG1-Pad52)") (class "Default")
      (node (ref "U2") (pin "52") (pinfunction "(RD)PG1_52") (pintype "bidirectional"))
    )
    (net (code "117") (name "unconnected-(U2-(SS{slash}PCINT0)PB0-Pad19)") (class "Default")
      (node (ref "U2") (pin "19") (pinfunction "(SS/PCINT0)PB0_19") (pintype "bidirectional"))
    )
    (net (code "118") (name "unconnected-(U2-(T1)PD6-Pad49)") (class "Default")
      (node (ref "U2") (pin "49") (pinfunction "(T1)PD6_49") (pintype "bidirectional"))
    )
    (net (code "119") (name "unconnected-(U2-(T3{slash}INT6)PE6-Pad8)") (class "Default")
      (node (ref "U2") (pin "8") (pinfunction "(T3/INT6)PE6_8") (pintype "bidirectional"))
    )
    (net (code "120") (name "unconnected-(U2-(TOSC1)PG4-Pad29)") (class "Default")
      (node (ref "U2") (pin "29") (pinfunction "(TOSC1)PG4_29") (pintype "bidirectional"))
    )
    (net (code "121") (name "unconnected-(U2-(TOSC2)PG3-Pad28)") (class "Default")
      (node (ref "U2") (pin "28") (pinfunction "(TOSC2)PG3_28") (pintype "bidirectional"))
    )
    (net (code "122") (name "unconnected-(U2-(WR)PG0-Pad51)") (class "Default")
      (node (ref "U2") (pin "51") (pinfunction "(WR)PG0_51") (pintype "bidirectional"))
    )
    (net (code "123") (name "unconnected-(U2-(XCK0{slash}AIN0)PE2-Pad4)") (class "Default")
      (node (ref "U2") (pin "4") (pinfunction "(XCK0/AIN0)PE2_4") (pintype "bidirectional"))
    )
    (net (code "124") (name "unconnected-(U2-(XCK1)PD5-Pad48)") (class "Default")
      (node (ref "U2") (pin "48") (pinfunction "(XCK1)PD5_48") (pintype "bidirectional"))
    )
    (net (code "125") (name "unconnected-(U2-PH2(XCK2)-Pad14)") (class "Default")
      (node (ref "U2") (pin "14") (pinfunction "PH2(XCK2)_14") (pintype "bidirectional"))
    )
    (net (code "126") (name "unconnected-(U2-PH3(OC4A)-Pad15)") (class "Default")
      (node (ref "U2") (pin "15") (pinfunction "PH3(OC4A)_15") (pintype "bidirectional"))
    )
    (net (code "127") (name "unconnected-(U2-PH4(OC4B)-Pad16)") (class "Default")
      (node (ref "U2") (pin "16") (pinfunction "PH4(OC4B)_16") (pintype "bidirectional"))
    )
    (net (code "128") (name "unconnected-(U2-PH5(OC4C)-Pad17)") (class "Default")
      (node (ref "U2") (pin "17") (pinfunction "PH5(OC4C)_17") (pintype "bidirectional"))
    )
    (net (code "129") (name "unconnected-(U2-PH6(OC2B)-Pad18)") (class "Default")
      (node (ref "U2") (pin "18") (pinfunction "PH6(OC2B)_18") (pintype "bidirectional"))
    )
    (net (code "130") (name "unconnected-(U2-PH7(T4)-Pad27)") (class "Default")
      (node (ref "U2") (pin "27") (pinfunction "PH7(T4)_27") (pintype "bidirectional"))
    )
    (net (code "131") (name "unconnected-(U2-PJ2(XCK3{slash}PCINT11)-Pad65)") (class "Default")
      (node (ref "U2") (pin "65") (pinfunction "PJ2(XCK3/PCINT11)_65") (pintype "bidirectional"))
    )
    (net (code "132") (name "unconnected-(U2-PJ3(PCINT12)-Pad66)") (class "Default")
      (node (ref "U2") (pin "66") (pinfunction "PJ3(PCINT12)_66") (pintype "bidirectional"))
    )
    (net (code "133") (name "unconnected-(U2-PJ4(PCINT13)-Pad67)") (class "Default")
      (node (ref "U2") (pin "67") (pinfunction "PJ4(PCINT13)_67") (pintype "bidirectional"))
    )
    (net (code "134") (name "unconnected-(U2-PJ5(PCINT14)-Pad68)") (class "Default")
      (node (ref "U2") (pin "68") (pinfunction "PJ5(PCINT14)_68") (pintype "bidirectional"))
    )
    (net (code "135") (name "unconnected-(U2-PJ6(PCINT15)-Pad69)") (class "Default")
      (node (ref "U2") (pin "69") (pinfunction "PJ6(PCINT15)_69") (pintype "bidirectional"))
    )
    (net (code "136") (name "unconnected-(U2-PJ7-Pad79)") (class "Default")
      (node (ref "U2") (pin "79") (pinfunction "PJ7_79") (pintype "bidirectional"))
    )
    (net (code "137") (name "unconnected-(U2-PK0(ADC8{slash}PCINT16)-Pad89)") (class "Default")
      (node (ref "U2") (pin "89") (pinfunction "PK0(ADC8/PCINT16)_89") (pintype "bidirectional"))
    )
    (net (code "138") (name "unconnected-(U2-PK1(ADC9{slash}PCINT17)-Pad88)") (class "Default")
      (node (ref "U2") (pin "88") (pinfunction "PK1(ADC9/PCINT17)_88") (pintype "bidirectional"))
    )
    (net (code "139") (name "unconnected-(U2-PK2(ADC10{slash}PCINT18)-Pad87)") (class "Default")
      (node (ref "U2") (pin "87") (pinfunction "PK2(ADC10/PCINT18)_87") (pintype "bidirectional"))
    )
    (net (code "140") (name "unconnected-(U2-PK3(ADC11{slash}PCINT19)-Pad86)") (class "Default")
      (node (ref "U2") (pin "86") (pinfunction "PK3(ADC11/PCINT19)_86") (pintype "bidirectional"))
    )
    (net (code "141") (name "unconnected-(U2-PK4(ADC12{slash}PCINT20)-Pad85)") (class "Default")
      (node (ref "U2") (pin "85") (pinfunction "PK4(ADC12/PCINT20)_85") (pintype "bidirectional"))
    )
    (net (code "142") (name "unconnected-(U2-PK5(ADC13{slash}PCINT21)-Pad84)") (class "Default")
      (node (ref "U2") (pin "84") (pinfunction "PK5(ADC13/PCINT21)_84") (pintype "bidirectional"))
    )
    (net (code "143") (name "unconnected-(U2-PK6(ADC14{slash}PCINT22)-Pad83)") (class "Default")
      (node (ref "U2") (pin "83") (pinfunction "PK6(ADC14/PCINT22)_83") (pintype "bidirectional"))
    )
    (net (code "144") (name "unconnected-(U2-PK7(ADC15{slash}PCINT23)-Pad82)") (class "Default")
      (node (ref "U2") (pin "82") (pinfunction "PK7(ADC15/PCINT23)_82") (pintype "bidirectional"))
    )
    (net (code "145") (name "unconnected-(U2-PL0(ICP4)-Pad35)") (class "Default")
      (node (ref "U2") (pin "35") (pinfunction "PL0(ICP4)_35") (pintype "bidirectional"))
    )
    (net (code "146") (name "unconnected-(U2-PL1(ICP5)-Pad36)") (class "Default")
      (node (ref "U2") (pin "36") (pinfunction "PL1(ICP5)_36") (pintype "bidirectional"))
    )
    (net (code "147") (name "unconnected-(U2-PL2(T5)-Pad37)") (class "Default")
      (node (ref "U2") (pin "37") (pinfunction "PL2(T5)_37") (pintype "bidirectional"))
    )
    (net (code "148") (name "unconnected-(U2-PL3(OC5A)-Pad38)") (class "Default")
      (node (ref "U2") (pin "38") (pinfunction "PL3(OC5A)_38") (pintype "bidirectional"))
    )
    (net (code "149") (name "unconnected-(U2-PL4(OC5B)-Pad39)") (class "Default")
      (node (ref "U2") (pin "39") (pinfunction "PL4(OC5B)_39") (pintype "bidirectional"))
    )
    (net (code "150") (name "unconnected-(U2-PL5(OC5C)-Pad40)") (class "Default")
      (node (ref "U2") (pin "40") (pinfunction "PL5(OC5C)_40") (pintype "bidirectional"))
    )
    (net (code "151") (name "unconnected-(U2-PL6-Pad41)") (class "Default")
      (node (ref "U2") (pin "41") (pinfunction "PL6_41") (pintype "bidirectional"))
    )
    (net (code "152") (name "unconnected-(U2-PL7-Pad42)") (class "Default")
      (node (ref "U2") (pin "42") (pinfunction "PL7_42") (pintype "bidirectional"))
    )
    (net (code "153") (name "unconnected-(U3-BP-Pad4)") (class "Default")
      (node (ref "U3") (pin "4") (pinfunction "BP_4") (pintype "input"))
    )
  )
)
